# Qwiic_Relay.net
KiCad netlist of a schematic drawn in EAGLE
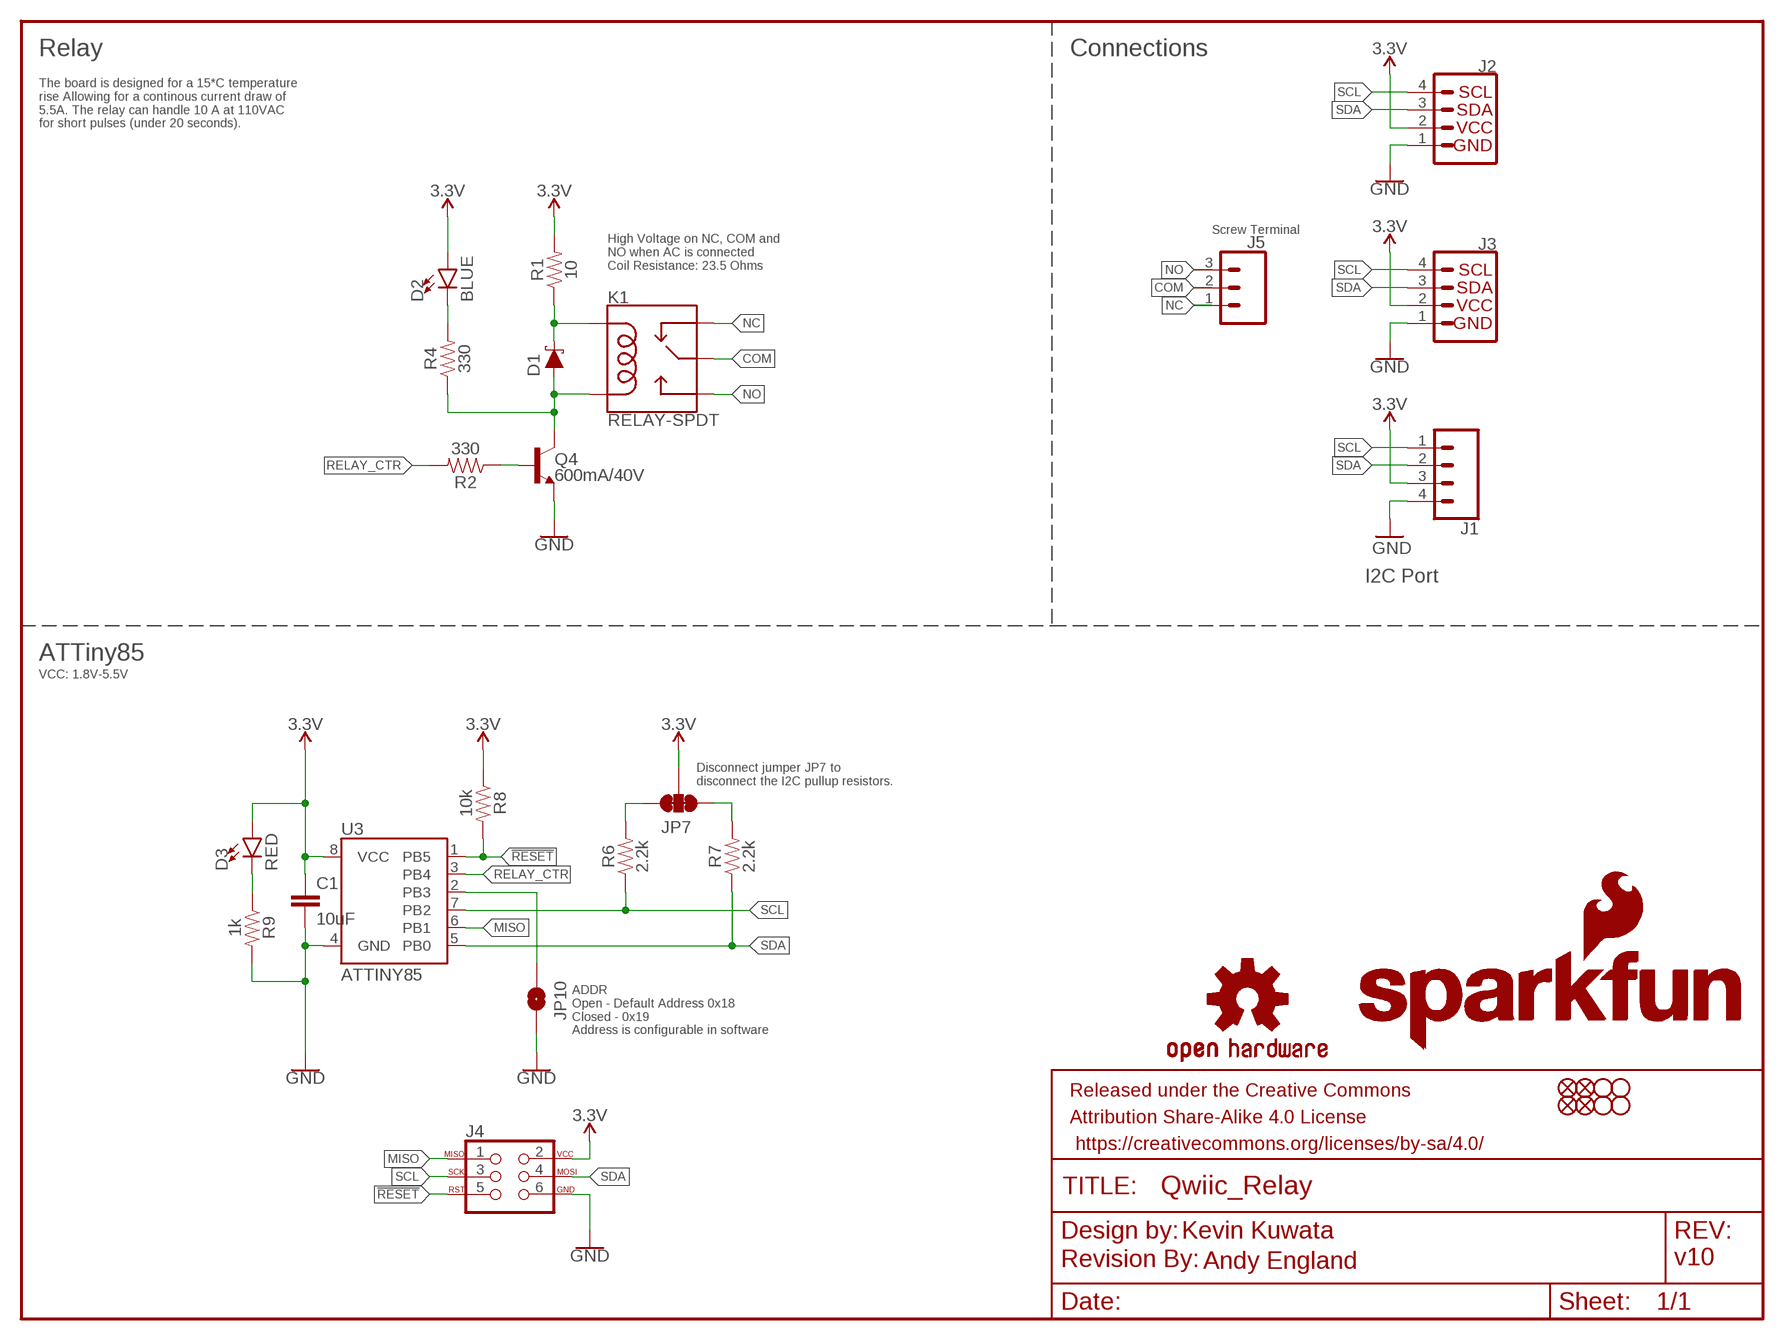
[diagram p0: schematic, sheet 1]

(export (version "E")
  (design (tool "Eeschema 10.0.6"))
  (components
    (comp (ref "C1")
      (value "10uF")
      (footprint "eagle-import:0603")
      (libsource (lib "eagle-import") (part "10UF-0603-6.3V-20%"))
    )
    (comp (ref "D1")
      (value "1A/23V/620mV")
      (footprint "eagle-import:SOD-323")
      (libsource (lib "eagle-import") (part "DIODE-SCHOTTKY-BAT20J"))
    )
    (comp (ref "D2")
      (value "BLUE")
      (footprint "eagle-import:LED-0603")
      (libsource (lib "eagle-import") (part "LED-BLUE0603"))
    )
    (comp (ref "D3")
      (value "RED")
      (footprint "eagle-import:LED-0603")
      (libsource (lib "eagle-import") (part "LED-RED0603"))
    )
    (comp (ref "FRAME1")
      (value "FRAME-LETTER")
      (footprint "eagle-import:CREATIVE_COMMONS")
      (libsource (lib "eagle-import") (part "FRAME-LETTER"))
    )
    (comp (ref "J1")
      (value "CONN_041X04_NO_SILK")
      (footprint "eagle-import:1X04_NO_SILK")
      (libsource (lib "eagle-import") (part "CONN_041X04_NO_SILK"))
    )
    (comp (ref "J2")
      (value "QWIIC_CONNECTORJS-1MM")
      (footprint "eagle-import:1X04_1MM_RA")
      (libsource (lib "eagle-import") (part "QWIIC_CONNECTORJS-1MM"))
    )
    (comp (ref "J3")
      (value "QWIIC_CONNECTORJS-1MM")
      (footprint "eagle-import:1X04_1MM_RA")
      (libsource (lib "eagle-import") (part "QWIIC_CONNECTORJS-1MM"))
    )
    (comp (ref "J4")
      (value "AVR_SPI_PROG_3X2TESTPOINTS")
      (footprint "eagle-import:2X3_TEST_POINTS")
      (libsource (lib "eagle-import") (part "AVR_SPI_PROG_3X2TESTPOINTS"))
    )
    (comp (ref "J5")
      (value "CONN_03-SCREW-5MM")
      (footprint "eagle-import:SCREWTERMINAL-5MM-3")
      (libsource (lib "eagle-import") (part "CONN_03-SCREW-5MM"))
    )
    (comp (ref "JP1")
      (value "STAND-OFF")
      (footprint "eagle-import:STAND-OFF")
      (libsource (lib "eagle-import") (part "STAND-OFF"))
    )
    (comp (ref "JP2")
      (value "FIDUCIALUFIDUCIAL")
      (footprint "eagle-import:MICRO-FIDUCIAL")
      (libsource (lib "eagle-import") (part "FIDUCIALUFIDUCIAL"))
    )
    (comp (ref "JP3")
      (value "STAND-OFF")
      (footprint "eagle-import:STAND-OFF")
      (libsource (lib "eagle-import") (part "STAND-OFF"))
    )
    (comp (ref "JP4")
      (value "STAND-OFF")
      (footprint "eagle-import:STAND-OFF")
      (libsource (lib "eagle-import") (part "STAND-OFF"))
    )
    (comp (ref "JP5")
      (value "STAND-OFF")
      (footprint "eagle-import:STAND-OFF")
      (libsource (lib "eagle-import") (part "STAND-OFF"))
    )
    (comp (ref "JP6")
      (value "FIDUCIALUFIDUCIAL")
      (footprint "eagle-import:MICRO-FIDUCIAL")
      (libsource (lib "eagle-import") (part "FIDUCIALUFIDUCIAL"))
    )
    (comp (ref "JP7")
      (value "JUMPER-SMT_3_2-NC_TRACE_NO-SILK")
      (footprint "eagle-import:SMT-JUMPER_3_2-NC_TRACE_NO-SILK")
      (libsource (lib "eagle-import") (part "JUMPER-SMT_3_2-NC_TRACE_NO-SILK"))
    )
    (comp (ref "JP8")
      (value "FIDUCIALUFIDUCIAL")
      (footprint "eagle-import:MICRO-FIDUCIAL")
      (libsource (lib "eagle-import") (part "FIDUCIALUFIDUCIAL"))
    )
    (comp (ref "JP9")
      (value "FIDUCIALUFIDUCIAL")
      (footprint "eagle-import:MICRO-FIDUCIAL")
      (libsource (lib "eagle-import") (part "FIDUCIALUFIDUCIAL"))
    )
    (comp (ref "JP10")
      (value "JUMPER-SMT_2_NO_NO-SILK")
      (footprint "eagle-import:SMT-JUMPER_2_NO_NO-SILK")
      (libsource (lib "eagle-import") (part "JUMPER-SMT_2_NO_NO-SILK"))
    )
    (comp (ref "K1")
      (value "RELAY-SPDT")
      (footprint "eagle-import:RELAY_G5LE")
      (libsource (lib "eagle-import") (part "RELAY-SPDT"))
    )
    (comp (ref "LOGO1")
      (value "OSHW-LOGOMINI")
      (footprint "eagle-import:OSHW-LOGO-MINI")
      (libsource (lib "eagle-import") (part "OSHW-LOGOMINI"))
    )
    (comp (ref "LOGO2")
      (value "REVISION")
      (footprint "eagle-import:REVISION")
      (libsource (lib "eagle-import") (part "REVISION"))
    )
    (comp (ref "Q4")
      (value "600mA/40V")
      (footprint "eagle-import:SOT23-3")
      (libsource (lib "eagle-import") (part "TRANS_NPN-MMBT2222AL"))
    )
    (comp (ref "R1")
      (value "10")
      (footprint "eagle-import:0603")
      (libsource (lib "eagle-import") (part "10OHM-0603-1/10W-5%"))
    )
    (comp (ref "R2")
      (value "330")
      (footprint "eagle-import:0603")
      (libsource (lib "eagle-import") (part "330OHM-0603-1/10W-1%"))
    )
    (comp (ref "R4")
      (value "330")
      (footprint "eagle-import:0603")
      (libsource (lib "eagle-import") (part "330OHM-0603-1/10W-1%"))
    )
    (comp (ref "R6")
      (value "2.2k")
      (footprint "eagle-import:0603")
      (libsource (lib "eagle-import") (part "2.2KOHM-0603-1/10W-1%"))
    )
    (comp (ref "R7")
      (value "2.2k")
      (footprint "eagle-import:0603")
      (libsource (lib "eagle-import") (part "2.2KOHM-0603-1/10W-1%"))
    )
    (comp (ref "R8")
      (value "10k")
      (footprint "eagle-import:0603")
      (libsource (lib "eagle-import") (part "10KOHM-0603-1/10W-1%"))
    )
    (comp (ref "R9")
      (value "1k")
      (footprint "eagle-import:0603")
      (libsource (lib "eagle-import") (part "1KOHM-0603-1/10W-1%"))
    )
    (comp (ref "U$3")
      (value "SFE_LOGO_NAME.1_INCH")
      (footprint "eagle-import:SFE_LOGO_NAME_.1")
      (libsource (lib "eagle-import") (part "SFE_LOGO_NAME.1_INCH"))
    )
    (comp (ref "U$4")
      (value "SFE_LOGO_NAME_FLAME.1_INCH")
      (footprint "eagle-import:SFE_LOGO_NAME_FLAME_.1")
      (libsource (lib "eagle-import") (part "SFE_LOGO_NAME_FLAME.1_INCH"))
    )
    (comp (ref "U3")
      (value "ATTINY85")
      (footprint "eagle-import:ATTINY85")
      (libsource (lib "eagle-import") (part "ATTINY85"))
    )
  )
  (nets
    (net (code "1") (name "/~{RESET}") (class "Default")
      (node (ref "J4") (pin "5") (pinfunction "5_5") (pintype "passive"))
      (node (ref "R8") (pin "2") (pinfunction "2_2") (pintype "passive"))
      (node (ref "U3") (pin "1") (pinfunction "PB5_1") (pintype "bidirectional"))
    )
    (net (code "2") (name "3.3V") (class "Default")
      (node (ref "C1") (pin "1") (pinfunction "1_1") (pintype "passive"))
      (node (ref "D2") (pin "A") (pinfunction "A_A") (pintype "passive"))
      (node (ref "D3") (pin "A") (pinfunction "A_A") (pintype "passive"))
      (node (ref "J1") (pin "3") (pinfunction "3_3") (pintype "passive"))
      (node (ref "J2") (pin "2") (pinfunction "2_2") (pintype "power_in"))
      (node (ref "J3") (pin "2") (pinfunction "2_2") (pintype "power_in"))
      (node (ref "J4") (pin "2") (pinfunction "2_2") (pintype "passive"))
      (node (ref "JP7") (pin "2") (pinfunction "2_2") (pintype "passive"))
      (node (ref "R1") (pin "2") (pinfunction "2_2") (pintype "passive"))
      (node (ref "R8") (pin "1") (pinfunction "1_1") (pintype "passive"))
      (node (ref "U3") (pin "8") (pinfunction "VCC_8") (pintype "bidirectional"))
    )
    (net (code "3") (name "COM") (class "Default")
      (node (ref "J5") (pin "2") (pinfunction "2_2") (pintype "passive"))
      (node (ref "K1") (pin "1") (pinfunction "MAIN_1") (pintype "bidirectional"))
    )
    (net (code "4") (name "GND") (class "Default")
      (node (ref "C1") (pin "2") (pinfunction "2_2") (pintype "passive"))
      (node (ref "J1") (pin "4") (pinfunction "4_4") (pintype "passive"))
      (node (ref "J2") (pin "1") (pinfunction "1_1") (pintype "power_in"))
      (node (ref "J3") (pin "1") (pinfunction "1_1") (pintype "power_in"))
      (node (ref "J4") (pin "6") (pinfunction "6_6") (pintype "passive"))
      (node (ref "JP10") (pin "2") (pinfunction "2_2") (pintype "passive"))
      (node (ref "Q4") (pin "2") (pinfunction "E_2") (pintype "passive"))
      (node (ref "R9") (pin "2") (pinfunction "2_2") (pintype "passive"))
      (node (ref "U3") (pin "4") (pinfunction "GND_4") (pintype "bidirectional"))
    )
    (net (code "5") (name "MISO") (class "Default")
      (node (ref "J4") (pin "1") (pinfunction "1_1") (pintype "passive"))
      (node (ref "U3") (pin "6") (pinfunction "PB1_6") (pintype "bidirectional"))
    )
    (net (code "6") (name "NC") (class "Default")
      (node (ref "J5") (pin "1") (pinfunction "1_1") (pintype "passive"))
      (node (ref "K1") (pin "4") (pinfunction "NC_4") (pintype "bidirectional"))
    )
    (net (code "7") (name "NO") (class "Default")
      (node (ref "J5") (pin "3") (pinfunction "3_3") (pintype "passive"))
      (node (ref "K1") (pin "3") (pinfunction "NO_3") (pintype "bidirectional"))
    )
    (net (code "8") (name "Net-(D2-PadC)") (class "Default")
      (node (ref "D2") (pin "C") (pinfunction "C_C") (pintype "passive"))
      (node (ref "R4") (pin "2") (pinfunction "2_2") (pintype "passive"))
    )
    (net (code "9") (name "Net-(D3-PadC)") (class "Default")
      (node (ref "D3") (pin "C") (pinfunction "C_C") (pintype "passive"))
      (node (ref "R9") (pin "1") (pinfunction "1_1") (pintype "passive"))
    )
    (net (code "10") (name "Net-(JP7-Pad1)") (class "Default")
      (node (ref "JP7") (pin "1") (pinfunction "1_1") (pintype "passive"))
      (node (ref "R7") (pin "2") (pinfunction "2_2") (pintype "passive"))
    )
    (net (code "11") (name "Net-(JP7-Pad3)") (class "Default")
      (node (ref "JP7") (pin "3") (pinfunction "3_3") (pintype "passive"))
      (node (ref "R6") (pin "2") (pinfunction "2_2") (pintype "passive"))
    )
    (net (code "12") (name "Net-(K1-COIL1)") (class "Default")
      (node (ref "D1") (pin "C") (pinfunction "C_C") (pintype "passive"))
      (node (ref "K1") (pin "2") (pinfunction "COIL1_2") (pintype "bidirectional"))
      (node (ref "R1") (pin "1") (pinfunction "1_1") (pintype "passive"))
    )
    (net (code "13") (name "Net-(K1-COIL2)") (class "Default")
      (node (ref "D1") (pin "A") (pinfunction "A_A") (pintype "passive"))
      (node (ref "K1") (pin "5") (pinfunction "COIL2_5") (pintype "bidirectional"))
      (node (ref "Q4") (pin "3") (pinfunction "C_3") (pintype "passive"))
      (node (ref "R4") (pin "1") (pinfunction "1_1") (pintype "passive"))
    )
    (net (code "14") (name "Net-(Q4-B)") (class "Default")
      (node (ref "Q4") (pin "1") (pinfunction "B_1") (pintype "passive"))
      (node (ref "R2") (pin "1") (pinfunction "1_1") (pintype "passive"))
    )
    (net (code "15") (name "Net-(U3-PB3)") (class "Default")
      (node (ref "JP10") (pin "1") (pinfunction "1_1") (pintype "passive"))
      (node (ref "U3") (pin "2") (pinfunction "PB3_2") (pintype "bidirectional"))
    )
    (net (code "16") (name "RELAY_CTR") (class "Default")
      (node (ref "R2") (pin "2") (pinfunction "2_2") (pintype "passive"))
      (node (ref "U3") (pin "3") (pinfunction "PB4_3") (pintype "bidirectional"))
    )
    (net (code "17") (name "SCL") (class "Default")
      (node (ref "J1") (pin "1") (pinfunction "1_1") (pintype "passive"))
      (node (ref "J2") (pin "4") (pinfunction "4_4") (pintype "passive"))
      (node (ref "J3") (pin "4") (pinfunction "4_4") (pintype "passive"))
      (node (ref "J4") (pin "3") (pinfunction "3_3") (pintype "passive"))
      (node (ref "R6") (pin "1") (pinfunction "1_1") (pintype "passive"))
      (node (ref "U3") (pin "7") (pinfunction "PB2_7") (pintype "bidirectional"))
    )
    (net (code "18") (name "SDA") (class "Default")
      (node (ref "J1") (pin "2") (pinfunction "2_2") (pintype "passive"))
      (node (ref "J2") (pin "3") (pinfunction "3_3") (pintype "passive"))
      (node (ref "J3") (pin "3") (pinfunction "3_3") (pintype "passive"))
      (node (ref "J4") (pin "4") (pinfunction "4_4") (pintype "passive"))
      (node (ref "R7") (pin "1") (pinfunction "1_1") (pintype "passive"))
      (node (ref "U3") (pin "5") (pinfunction "PB0_5") (pintype "bidirectional"))
    )
  )
)
